# Edwin_GM12006.net
KiCad netlist of a schematic drawn in EAGLE
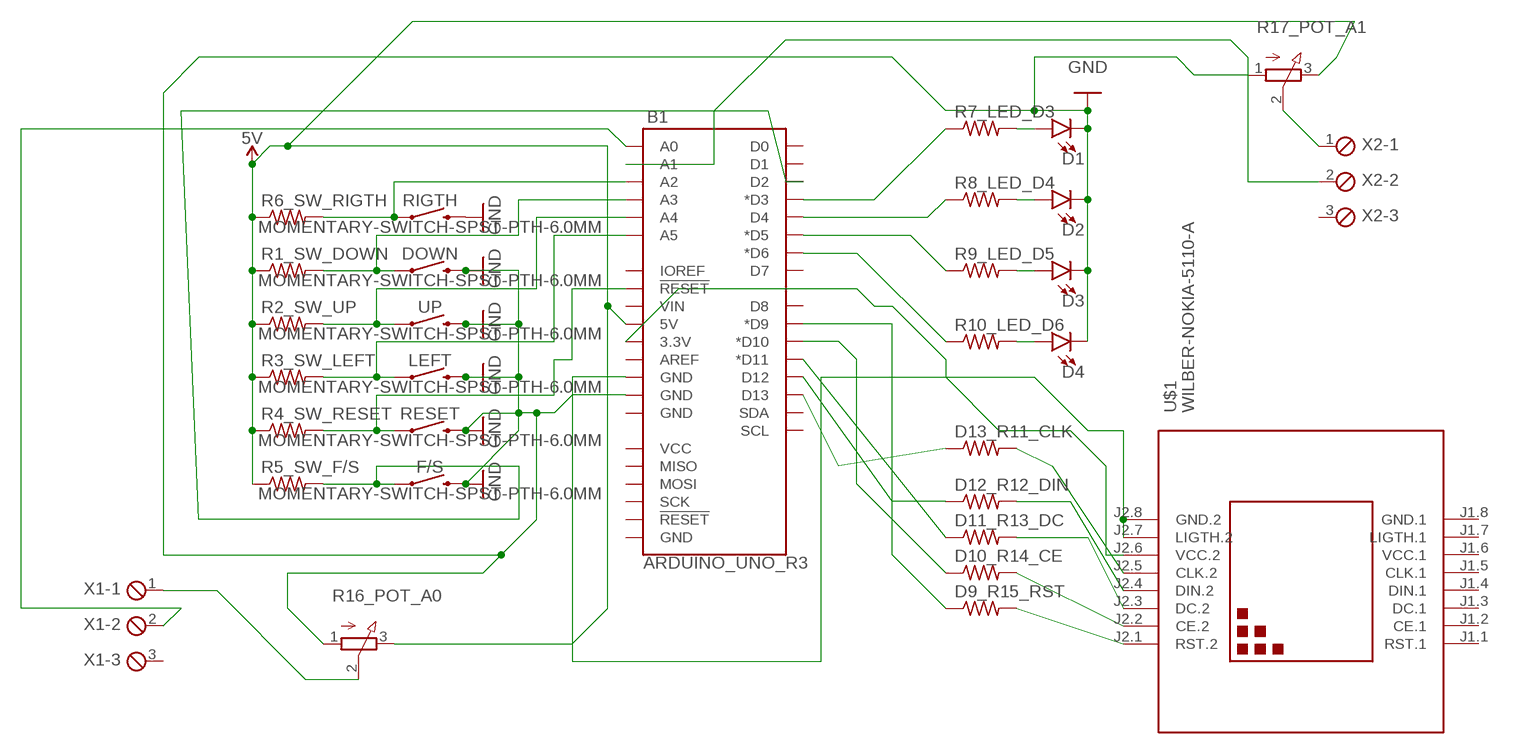
[diagram p0: schematic, sheet 1]

(export (version "E")
  (design (tool "Eeschema 10.0.6"))
  (components
    (comp (ref "B1")
      (value "ARDUINO_UNO_R3")
      (footprint "eagle-import:ARDUINO_R3")
      (libsource (lib "eagle-import") (part "ARDUINO_UNO_R3"))
    )
    (comp (ref "D1")
      (value "LED5MM")
      (footprint "eagle-import:LED_5MM")
      (libsource (lib "eagle-import") (part "LED5MM"))
    )
    (comp (ref "D2")
      (value "LED5MM")
      (footprint "eagle-import:LED_5MM")
      (libsource (lib "eagle-import") (part "LED5MM"))
    )
    (comp (ref "D3")
      (value "LED5MM")
      (footprint "eagle-import:LED_5MM")
      (libsource (lib "eagle-import") (part "LED5MM"))
    )
    (comp (ref "D4")
      (value "LED5MM")
      (footprint "eagle-import:LED_5MM")
      (libsource (lib "eagle-import") (part "LED5MM"))
    )
    (comp (ref "D9_R15_RST")
      (value "R-US_0207/10")
      (footprint "eagle-import:0207_10")
      (libsource (lib "eagle-import") (part "R-US_0207/10"))
    )
    (comp (ref "D10_R14_CE")
      (value "R-US_0207/10")
      (footprint "eagle-import:0207_10")
      (libsource (lib "eagle-import") (part "R-US_0207/10"))
    )
    (comp (ref "D11_R13_DC")
      (value "R-US_0207/10")
      (footprint "eagle-import:0207_10")
      (libsource (lib "eagle-import") (part "R-US_0207/10"))
    )
    (comp (ref "D12_R12_DIN")
      (value "R-US_0207/10")
      (footprint "eagle-import:0207_10")
      (libsource (lib "eagle-import") (part "R-US_0207/10"))
    )
    (comp (ref "D13_R11_CLK")
      (value "R-US_0207/10")
      (footprint "eagle-import:0207_10")
      (libsource (lib "eagle-import") (part "R-US_0207/10"))
    )
    (comp (ref "DOWN")
      (value "MOMENTARY-SWITCH-SPST-PTH-6.0MM")
      (footprint "eagle-import:TACTILE_SWITCH_PTH_6.0MM")
      (libsource (lib "eagle-import") (part "MOMENTARY-SWITCH-SPST-PTH-6.0MM"))
    )
    (comp (ref "F/S")
      (value "MOMENTARY-SWITCH-SPST-PTH-6.0MM")
      (footprint "eagle-import:TACTILE_SWITCH_PTH_6.0MM")
      (libsource (lib "eagle-import") (part "MOMENTARY-SWITCH-SPST-PTH-6.0MM"))
    )
    (comp (ref "LEFT")
      (value "MOMENTARY-SWITCH-SPST-PTH-6.0MM")
      (footprint "eagle-import:TACTILE_SWITCH_PTH_6.0MM")
      (libsource (lib "eagle-import") (part "MOMENTARY-SWITCH-SPST-PTH-6.0MM"))
    )
    (comp (ref "R1_SW_DOWN")
      (value "R-US_0207/10")
      (footprint "eagle-import:0207_10")
      (libsource (lib "eagle-import") (part "R-US_0207/10"))
    )
    (comp (ref "R2_SW_UP")
      (value "R-US_0207/10")
      (footprint "eagle-import:0207_10")
      (libsource (lib "eagle-import") (part "R-US_0207/10"))
    )
    (comp (ref "R3_SW_LEFT")
      (value "R-US_0207/10")
      (footprint "eagle-import:0207_10")
      (libsource (lib "eagle-import") (part "R-US_0207/10"))
    )
    (comp (ref "R4_SW_RESET")
      (value "R-US_0207/10")
      (footprint "eagle-import:0207_10")
      (libsource (lib "eagle-import") (part "R-US_0207/10"))
    )
    (comp (ref "R5_SW_F/S")
      (value "R-US_0207/10")
      (footprint "eagle-import:0207_10")
      (libsource (lib "eagle-import") (part "R-US_0207/10"))
    )
    (comp (ref "R6_SW_RIGTH")
      (value "R-US_0207/10")
      (footprint "eagle-import:0207_10")
      (libsource (lib "eagle-import") (part "R-US_0207/10"))
    )
    (comp (ref "R7_LED_D3")
      (value "R-US_0207/10")
      (footprint "eagle-import:0207_10")
      (libsource (lib "eagle-import") (part "R-US_0207/10"))
    )
    (comp (ref "R8_LED_D4")
      (value "R-US_0207/10")
      (footprint "eagle-import:0207_10")
      (libsource (lib "eagle-import") (part "R-US_0207/10"))
    )
    (comp (ref "R9_LED_D5")
      (value "R-US_0207/10")
      (footprint "eagle-import:0207_10")
      (libsource (lib "eagle-import") (part "R-US_0207/10"))
    )
    (comp (ref "R10_LED_D6")
      (value "R-US_0207/10")
      (footprint "eagle-import:0207_10")
      (libsource (lib "eagle-import") (part "R-US_0207/10"))
    )
    (comp (ref "R16_POT_A0")
      (value "3RP/1610N")
      (footprint "eagle-import:3RP_1610N")
      (libsource (lib "eagle-import") (part "3RP/1610N"))
    )
    (comp (ref "R17_POT_A1")
      (value "3RP/1610N")
      (footprint "eagle-import:3RP_1610N")
      (libsource (lib "eagle-import") (part "3RP/1610N"))
    )
    (comp (ref "RESET")
      (value "MOMENTARY-SWITCH-SPST-PTH-6.0MM")
      (footprint "eagle-import:TACTILE_SWITCH_PTH_6.0MM")
      (libsource (lib "eagle-import") (part "MOMENTARY-SWITCH-SPST-PTH-6.0MM"))
    )
    (comp (ref "RIGTH")
      (value "MOMENTARY-SWITCH-SPST-PTH-6.0MM")
      (footprint "eagle-import:TACTILE_SWITCH_PTH_6.0MM")
      (libsource (lib "eagle-import") (part "MOMENTARY-SWITCH-SPST-PTH-6.0MM"))
    )
    (comp (ref "U$1")
      (value "WILBER-NOKIA-5110-A")
      (footprint "eagle-import:WILBER-NOKIA-5110-A")
      (libsource (lib "eagle-import") (part "WILBER-NOKIA-5110-A"))
    )
    (comp (ref "UP")
      (value "MOMENTARY-SWITCH-SPST-PTH-6.0MM")
      (footprint "eagle-import:TACTILE_SWITCH_PTH_6.0MM")
      (libsource (lib "eagle-import") (part "MOMENTARY-SWITCH-SPST-PTH-6.0MM"))
    )
    (comp (ref "X1")
      (value "MPT3")
      (footprint "eagle-import:3POL254")
      (libsource (lib "eagle-import") (part "MPT3"))
    )
    (comp (ref "X2")
      (value "MPT3")
      (footprint "eagle-import:3POL254")
      (libsource (lib "eagle-import") (part "MPT3"))
    )
  )
  (nets
    (net (code "1") (name "/CE.1") (class "Default")
      (node (ref "U$1") (pin "J1.2") (pinfunction "CE.1_J1.2") (pintype "power_in"))
    )
    (net (code "2") (name "/RST.1") (class "Default")
      (node (ref "U$1") (pin "J1.1") (pinfunction "RST.1_J1.1") (pintype "power_in"))
    )
    (net (code "3") (name "5V") (class "Default")
      (node (ref "B1") (pin "5V") (pinfunction "5V_5V") (pintype "bidirectional"))
      (node (ref "R16_POT_A0") (pin "3") (pinfunction "E_3") (pintype "passive"))
      (node (ref "R17_POT_A1") (pin "3") (pinfunction "E_3") (pintype "passive"))
      (node (ref "R1_SW_DOWN") (pin "1") (pinfunction "1_1") (pintype "passive"))
      (node (ref "R2_SW_UP") (pin "1") (pinfunction "1_1") (pintype "passive"))
      (node (ref "R3_SW_LEFT") (pin "1") (pinfunction "1_1") (pintype "passive"))
      (node (ref "R4_SW_RESET") (pin "1") (pinfunction "1_1") (pintype "passive"))
      (node (ref "R5_SW_F/S") (pin "1") (pinfunction "1_1") (pintype "passive"))
      (node (ref "R6_SW_RIGTH") (pin "1") (pinfunction "1_1") (pintype "passive"))
    )
    (net (code "4") (name "GND") (class "Default")
      (node (ref "B1") (pin "GND@3") (pinfunction "GND_GND@3") (pintype "bidirectional"))
      (node (ref "D1") (pin "K") (pinfunction "C_K") (pintype "passive"))
      (node (ref "D2") (pin "K") (pinfunction "C_K") (pintype "passive"))
      (node (ref "D3") (pin "K") (pinfunction "C_K") (pintype "passive"))
      (node (ref "D4") (pin "K") (pinfunction "C_K") (pintype "passive"))
      (node (ref "DOWN") (pin "3") (pinfunction "2_3") (pintype "passive"))
      (node (ref "F/S") (pin "3") (pinfunction "2_3") (pintype "passive"))
      (node (ref "LEFT") (pin "3") (pinfunction "2_3") (pintype "passive"))
      (node (ref "R16_POT_A0") (pin "1") (pinfunction "A_1") (pintype "passive"))
      (node (ref "R17_POT_A1") (pin "1") (pinfunction "A_1") (pintype "passive"))
      (node (ref "RESET") (pin "3") (pinfunction "2_3") (pintype "passive"))
      (node (ref "RIGTH") (pin "3") (pinfunction "2_3") (pintype "passive"))
      (node (ref "UP") (pin "3") (pinfunction "2_3") (pintype "passive"))
    )
    (net (code "5") (name "Net-(B1-*D3)") (class "Default")
      (node (ref "B1") (pin "D3") (pinfunction "*D3_D3") (pintype "bidirectional"))
      (node (ref "R7_LED_D3") (pin "1") (pinfunction "1_1") (pintype "passive"))
    )
    (net (code "6") (name "Net-(B1-*D5)") (class "Default")
      (node (ref "B1") (pin "D5") (pinfunction "*D5_D5") (pintype "bidirectional"))
      (node (ref "R9_LED_D5") (pin "1") (pinfunction "1_1") (pintype "passive"))
    )
    (net (code "7") (name "Net-(B1-*D6)") (class "Default")
      (node (ref "B1") (pin "D6") (pinfunction "*D6_D6") (pintype "bidirectional"))
      (node (ref "R10_LED_D6") (pin "1") (pinfunction "1_1") (pintype "passive"))
    )
    (net (code "8") (name "Net-(B1-*D9)") (class "Default")
      (node (ref "B1") (pin "D9") (pinfunction "*D9_D9") (pintype "bidirectional"))
      (node (ref "D9_R15_RST") (pin "1") (pinfunction "1_1") (pintype "passive"))
    )
    (net (code "9") (name "Net-(B1-*D10)") (class "Default")
      (node (ref "B1") (pin "D10") (pinfunction "*D10_D10") (pintype "bidirectional"))
      (node (ref "D10_R14_CE") (pin "1") (pinfunction "1_1") (pintype "passive"))
    )
    (net (code "10") (name "Net-(B1-*D11)") (class "Default")
      (node (ref "B1") (pin "D11") (pinfunction "*D11_D11") (pintype "bidirectional"))
      (node (ref "D11_R13_DC") (pin "1") (pinfunction "1_1") (pintype "passive"))
    )
    (net (code "11") (name "Net-(B1-PadA2)") (class "Default")
      (node (ref "B1") (pin "A2") (pinfunction "A2_A2") (pintype "bidirectional"))
      (node (ref "R6_SW_RIGTH") (pin "2") (pinfunction "2_2") (pintype "passive"))
      (node (ref "RIGTH") (pin "1") (pinfunction "1_1") (pintype "passive"))
    )
    (net (code "12") (name "Net-(B1-PadA3)") (class "Default")
      (node (ref "B1") (pin "A3") (pinfunction "A3_A3") (pintype "bidirectional"))
      (node (ref "DOWN") (pin "1") (pinfunction "1_1") (pintype "passive"))
      (node (ref "R1_SW_DOWN") (pin "2") (pinfunction "2_2") (pintype "passive"))
    )
    (net (code "13") (name "Net-(B1-PadA4)") (class "Default")
      (node (ref "B1") (pin "A4") (pinfunction "A4_A4") (pintype "bidirectional"))
      (node (ref "R2_SW_UP") (pin "2") (pinfunction "2_2") (pintype "passive"))
      (node (ref "UP") (pin "1") (pinfunction "1_1") (pintype "passive"))
    )
    (net (code "14") (name "Net-(B1-PadA5)") (class "Default")
      (node (ref "B1") (pin "A5") (pinfunction "A5_A5") (pintype "bidirectional"))
      (node (ref "LEFT") (pin "1") (pinfunction "1_1") (pintype "passive"))
      (node (ref "R3_SW_LEFT") (pin "2") (pinfunction "2_2") (pintype "passive"))
    )
    (net (code "15") (name "Net-(B1-PadD2)") (class "Default")
      (node (ref "B1") (pin "D2") (pinfunction "D2_D2") (pintype "bidirectional"))
      (node (ref "F/S") (pin "1") (pinfunction "1_1") (pintype "passive"))
      (node (ref "R5_SW_F/S") (pin "2") (pinfunction "2_2") (pintype "passive"))
    )
    (net (code "16") (name "Net-(B1-PadD4)") (class "Default")
      (node (ref "B1") (pin "D4") (pinfunction "D4_D4") (pintype "bidirectional"))
      (node (ref "R8_LED_D4") (pin "1") (pinfunction "1_1") (pintype "passive"))
    )
    (net (code "17") (name "Net-(B1-PadD12)") (class "Default")
      (node (ref "B1") (pin "D12") (pinfunction "D12_D12") (pintype "bidirectional"))
      (node (ref "D12_R12_DIN") (pin "1") (pinfunction "1_1") (pintype "passive"))
    )
    (net (code "18") (name "Net-(B1-PadD13)") (class "Default")
      (node (ref "B1") (pin "D13") (pinfunction "D13_D13") (pintype "bidirectional"))
      (node (ref "D13_R11_CLK") (pin "1") (pinfunction "1_1") (pintype "passive"))
    )
    (net (code "19") (name "Net-(B1-~{RESET}-PadRESET@1)") (class "Default")
      (node (ref "B1") (pin "RESET@1") (pinfunction "~{RESET}_RESET@1") (pintype "bidirectional"))
      (node (ref "R4_SW_RESET") (pin "2") (pinfunction "2_2") (pintype "passive"))
      (node (ref "RESET") (pin "1") (pinfunction "1_1") (pintype "passive"))
    )
    (net (code "20") (name "Net-(D1-PadA)") (class "Default")
      (node (ref "D1") (pin "A") (pinfunction "A_A") (pintype "passive"))
      (node (ref "R7_LED_D3") (pin "2") (pinfunction "2_2") (pintype "passive"))
    )
    (net (code "21") (name "Net-(D2-PadA)") (class "Default")
      (node (ref "D2") (pin "A") (pinfunction "A_A") (pintype "passive"))
      (node (ref "R8_LED_D4") (pin "2") (pinfunction "2_2") (pintype "passive"))
    )
    (net (code "22") (name "Net-(D3-PadA)") (class "Default")
      (node (ref "D3") (pin "A") (pinfunction "A_A") (pintype "passive"))
      (node (ref "R9_LED_D5") (pin "2") (pinfunction "2_2") (pintype "passive"))
    )
    (net (code "23") (name "Net-(D4-PadA)") (class "Default")
      (node (ref "D4") (pin "A") (pinfunction "A_A") (pintype "passive"))
      (node (ref "R10_LED_D6") (pin "2") (pinfunction "2_2") (pintype "passive"))
    )
    (net (code "24") (name "Net-(R16_POT_A0-S)") (class "Default")
      (node (ref "R16_POT_A0") (pin "2") (pinfunction "S_2") (pintype "passive"))
      (node (ref "X1") (pin "1") (pinfunction "1_1") (pintype "passive"))
    )
    (net (code "25") (name "Net-(R17_POT_A1-S)") (class "Default")
      (node (ref "R17_POT_A1") (pin "2") (pinfunction "S_2") (pintype "passive"))
      (node (ref "X2") (pin "1") (pinfunction "1_1") (pintype "passive"))
    )
    (net (code "26") (name "Net-(U$1-CE.2)") (class "Default")
      (node (ref "D10_R14_CE") (pin "2") (pinfunction "2_2") (pintype "passive"))
      (node (ref "U$1") (pin "J2.2") (pinfunction "CE.2_J2.2") (pintype "power_in"))
    )
    (net (code "27") (name "Net-(U$1-CLK.2)") (class "Default")
      (node (ref "D13_R11_CLK") (pin "2") (pinfunction "2_2") (pintype "passive"))
      (node (ref "U$1") (pin "J2.5") (pinfunction "CLK.2_J2.5") (pintype "bidirectional"))
    )
    (net (code "28") (name "Net-(U$1-DC.2)") (class "Default")
      (node (ref "D11_R13_DC") (pin "2") (pinfunction "2_2") (pintype "passive"))
      (node (ref "U$1") (pin "J2.3") (pinfunction "DC.2_J2.3") (pintype "bidirectional"))
    )
    (net (code "29") (name "Net-(U$1-DIN.2)") (class "Default")
      (node (ref "D12_R12_DIN") (pin "2") (pinfunction "2_2") (pintype "passive"))
      (node (ref "U$1") (pin "J2.4") (pinfunction "DIN.2_J2.4") (pintype "bidirectional"))
    )
    (net (code "30") (name "Net-(U$1-GND.2)") (class "Default")
      (node (ref "B1") (pin "GND@4") (pinfunction "GND_GND@4") (pintype "bidirectional"))
      (node (ref "U$1") (pin "J2.7") (pinfunction "LIGTH.2_J2.7") (pintype "bidirectional"))
      (node (ref "U$1") (pin "J2.8") (pinfunction "GND.2_J2.8") (pintype "input"))
    )
    (net (code "31") (name "Net-(U$1-RST.2)") (class "Default")
      (node (ref "D9_R15_RST") (pin "2") (pinfunction "2_2") (pintype "passive"))
      (node (ref "U$1") (pin "J2.1") (pinfunction "RST.2_J2.1") (pintype "power_in"))
    )
    (net (code "32") (name "Net-(U$1-VCC.2)") (class "Default")
      (node (ref "B1") (pin "3.3V") (pinfunction "3.3V_3.3V") (pintype "bidirectional"))
      (node (ref "U$1") (pin "J2.6") (pinfunction "VCC.2_J2.6") (pintype "bidirectional"))
    )
    (net (code "33") (name "Net-(X1B-1)") (class "Default")
      (node (ref "B1") (pin "A0") (pinfunction "A0_A0") (pintype "bidirectional"))
      (node (ref "X1") (pin "2") (pinfunction "1_2") (pintype "passive"))
    )
    (net (code "34") (name "Net-(X2B-1)") (class "Default")
      (node (ref "B1") (pin "A1") (pinfunction "A1_A1") (pintype "bidirectional"))
      (node (ref "X2") (pin "2") (pinfunction "1_2") (pintype "passive"))
    )
    (net (code "35") (name "unconnected-(B1-GND-PadGND@1)") (class "Default")
      (node (ref "B1") (pin "GND@1") (pinfunction "GND_GND@1") (pintype "bidirectional"))
    )
    (net (code "36") (name "unconnected-(B1-GND-PadGND@2)") (class "Default")
      (node (ref "B1") (pin "GND@2") (pinfunction "GND_GND@2") (pintype "bidirectional"))
    )
    (net (code "37") (name "unconnected-(B1-PadAREF)") (class "Default")
      (node (ref "B1") (pin "AREF") (pinfunction "AREF_AREF") (pintype "bidirectional"))
    )
    (net (code "38") (name "unconnected-(B1-PadD0)") (class "Default")
      (node (ref "B1") (pin "D0") (pinfunction "D0_D0") (pintype "bidirectional"))
    )
    (net (code "39") (name "unconnected-(B1-PadD1)") (class "Default")
      (node (ref "B1") (pin "D1") (pinfunction "D1_D1") (pintype "bidirectional"))
    )
    (net (code "40") (name "unconnected-(B1-PadD7)") (class "Default")
      (node (ref "B1") (pin "D7") (pinfunction "D7_D7") (pintype "bidirectional"))
    )
    (net (code "41") (name "unconnected-(B1-PadD8)") (class "Default")
      (node (ref "B1") (pin "D8") (pinfunction "D8_D8") (pintype "bidirectional"))
    )
    (net (code "42") (name "unconnected-(B1-PadIOREF)") (class "Default")
      (node (ref "B1") (pin "IOREF") (pinfunction "IOREF_IOREF") (pintype "bidirectional"))
    )
    (net (code "43") (name "unconnected-(B1-PadMISO)") (class "Default")
      (node (ref "B1") (pin "MISO") (pinfunction "MISO_MISO") (pintype "bidirectional"))
    )
    (net (code "44") (name "unconnected-(B1-PadMOSI)") (class "Default")
      (node (ref "B1") (pin "MOSI") (pinfunction "MOSI_MOSI") (pintype "bidirectional"))
    )
    (net (code "45") (name "unconnected-(B1-PadSCK)") (class "Default")
      (node (ref "B1") (pin "SCK") (pinfunction "SCK_SCK") (pintype "bidirectional"))
    )
    (net (code "46") (name "unconnected-(B1-PadSCL)") (class "Default")
      (node (ref "B1") (pin "SCL") (pinfunction "SCL_SCL") (pintype "bidirectional"))
    )
    (net (code "47") (name "unconnected-(B1-PadSDA)") (class "Default")
      (node (ref "B1") (pin "SDA") (pinfunction "SDA_SDA") (pintype "bidirectional"))
    )
    (net (code "48") (name "unconnected-(B1-PadVCC)") (class "Default")
      (node (ref "B1") (pin "VCC") (pinfunction "VCC_VCC") (pintype "bidirectional"))
    )
    (net (code "49") (name "unconnected-(B1-PadVIN)") (class "Default")
      (node (ref "B1") (pin "VIN") (pinfunction "VIN_VIN") (pintype "bidirectional"))
    )
    (net (code "50") (name "unconnected-(B1-~{RESET}-PadRESET@2)") (class "Default")
      (node (ref "B1") (pin "RESET@2") (pinfunction "~{RESET}_RESET@2") (pintype "bidirectional"))
    )
    (net (code "51") (name "unconnected-(U$1-CLK.1-PadJ1.5)") (class "Default")
      (node (ref "U$1") (pin "J1.5") (pinfunction "CLK.1_J1.5") (pintype "bidirectional"))
    )
    (net (code "52") (name "unconnected-(U$1-DC.1-PadJ1.3)") (class "Default")
      (node (ref "U$1") (pin "J1.3") (pinfunction "DC.1_J1.3") (pintype "bidirectional"))
    )
    (net (code "53") (name "unconnected-(U$1-DIN.1-PadJ1.4)") (class "Default")
      (node (ref "U$1") (pin "J1.4") (pinfunction "DIN.1_J1.4") (pintype "bidirectional"))
    )
    (net (code "54") (name "unconnected-(U$1-GND.1-PadJ1.8)") (class "Default")
      (node (ref "U$1") (pin "J1.8") (pinfunction "GND.1_J1.8") (pintype "input"))
    )
    (net (code "55") (name "unconnected-(U$1-LIGTH.1-PadJ1.7)") (class "Default")
      (node (ref "U$1") (pin "J1.7") (pinfunction "LIGTH.1_J1.7") (pintype "bidirectional"))
    )
    (net (code "56") (name "unconnected-(U$1-VCC.1-PadJ1.6)") (class "Default")
      (node (ref "U$1") (pin "J1.6") (pinfunction "VCC.1_J1.6") (pintype "bidirectional"))
    )
    (net (code "57") (name "unconnected-(X1C-1-Pad3)") (class "Default")
      (node (ref "X1") (pin "3") (pinfunction "1_3") (pintype "passive"))
    )
    (net (code "58") (name "unconnected-(X2C-1-Pad3)") (class "Default")
      (node (ref "X2") (pin "3") (pinfunction "1_3") (pintype "passive"))
    )
  )
)
